# UPDIMOD-v1_0.net
KiCad netlist of a schematic drawn in EAGLE
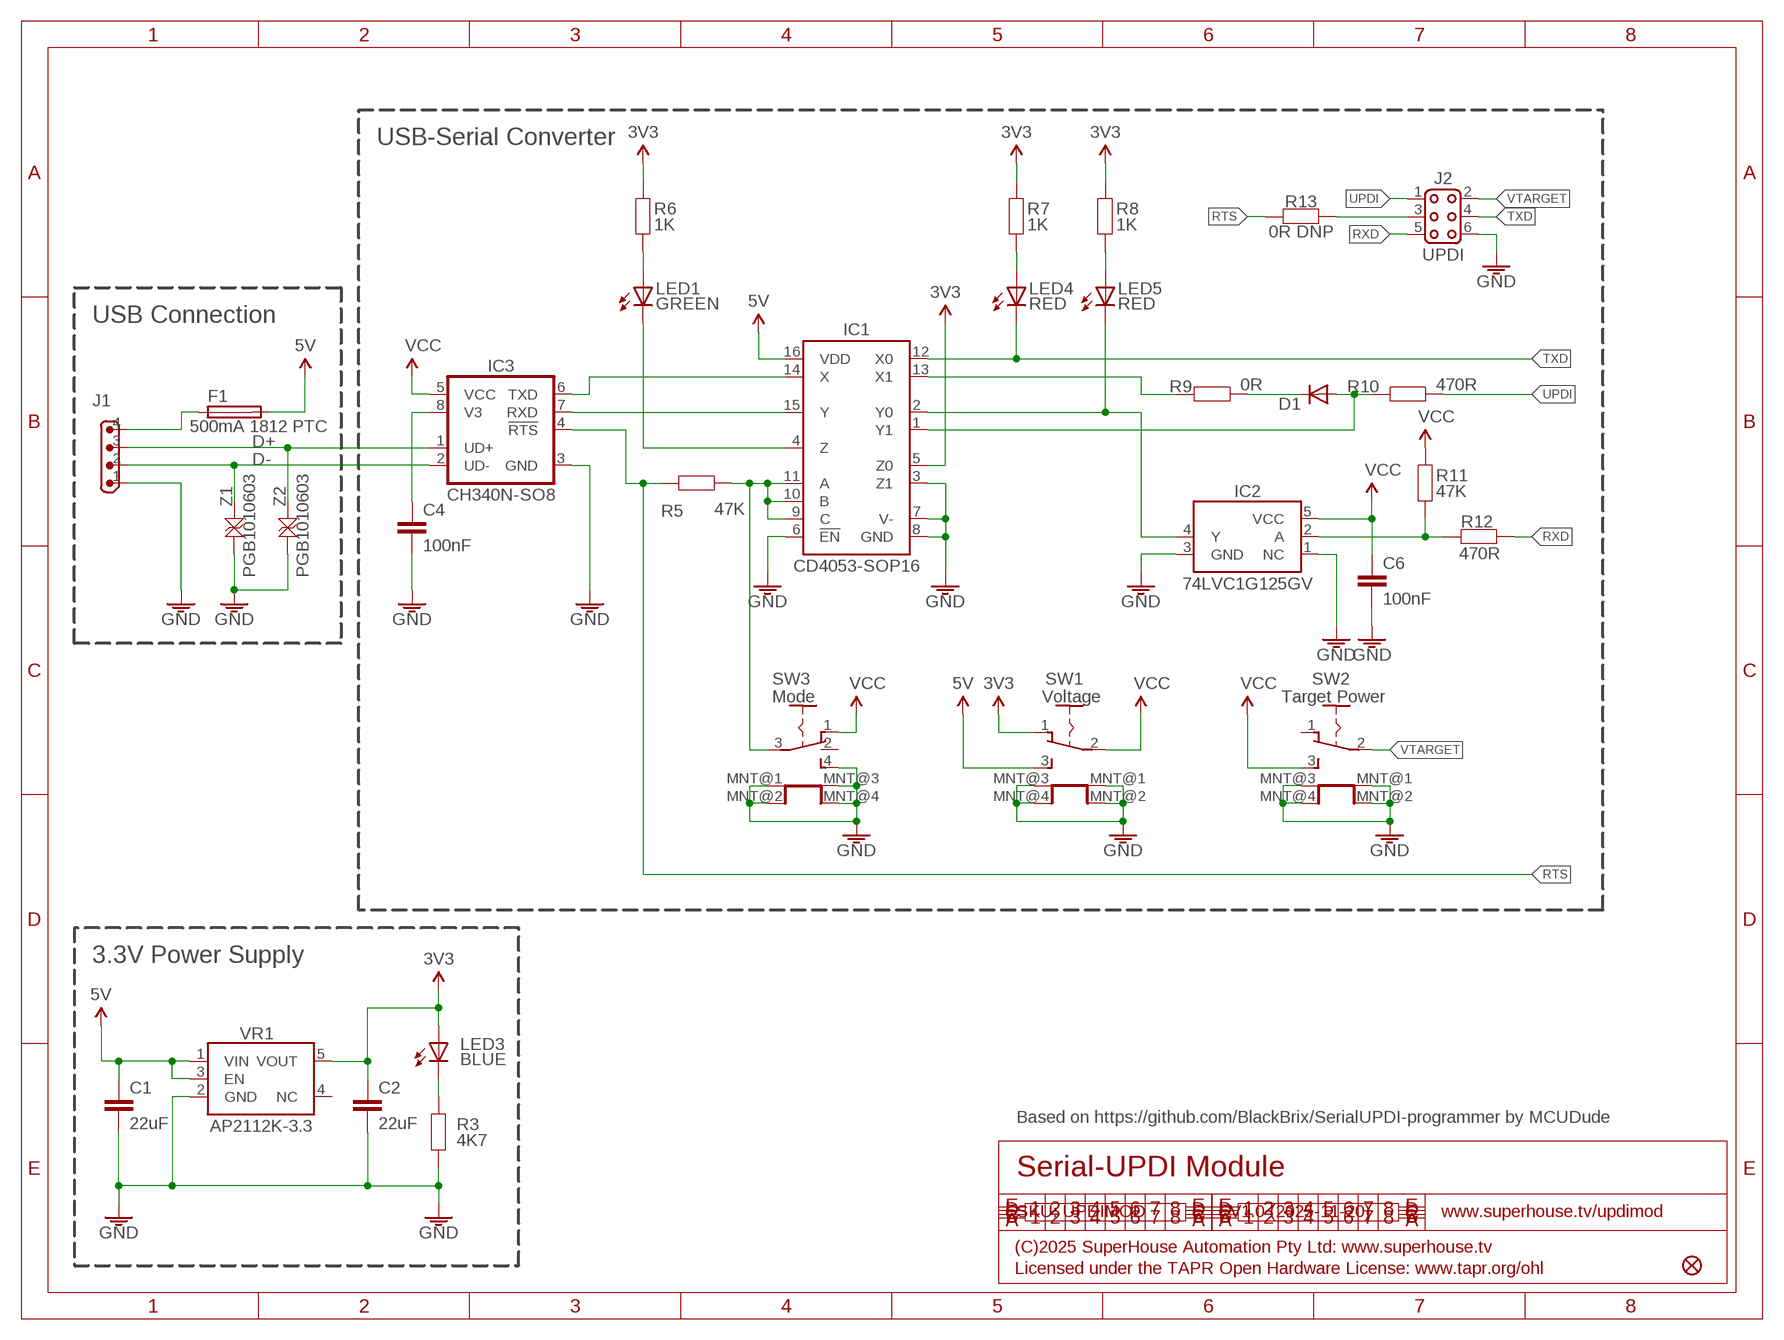
[diagram p0: schematic, sheet 1]

(export (version "E")
  (design (tool "Eeschema 10.0.6"))
  (components
    (comp (ref "C1")
      (value "22uF")
      (footprint "eagle-import:C0805")
      (libsource (lib "eagle-import") (part "CAP0805"))
    )
    (comp (ref "C2")
      (value "22uF")
      (footprint "eagle-import:C0805")
      (libsource (lib "eagle-import") (part "CAP0805"))
    )
    (comp (ref "C4")
      (value "100nF")
      (footprint "eagle-import:C0603")
      (libsource (lib "eagle-import") (part "SuperHouse-DiscreteSemi_11768461_CAP0603"))
    )
    (comp (ref "C6")
      (value "100nF")
      (footprint "eagle-import:C0603")
      (libsource (lib "eagle-import") (part "SuperHouse-DiscreteSemi_11768461_CAP0603"))
    )
    (comp (ref "D1")
      (value "DIODE-SOD123")
      (footprint "eagle-import:SOD-123")
      (libsource (lib "eagle-import") (part "DIODE-SOD123"))
    )
    (comp (ref "F1")
      (value "500mA 1812 PTC")
      (footprint "eagle-import:1206")
      (libsource (lib "eagle-import") (part "PTC-1206"))
    )
    (comp (ref "FID2")
      (value "FIDUCIAL1X2.5")
      (footprint "eagle-import:FIDUCIAL-1X2.5")
      (libsource (lib "eagle-import") (part "FIDUCIAL1X2.5"))
    )
    (comp (ref "IC1")
      (value "CD4053-SOP16")
      (footprint "eagle-import:SO16")
      (libsource (lib "eagle-import") (part "CD4053-SOP16"))
    )
    (comp (ref "IC2")
      (value "74LVC1G125GV")
      (footprint "eagle-import:SOT23-5")
      (libsource (lib "eagle-import") (part "74AHC1G14GW-SOT235"))
    )
    (comp (ref "IC3")
      (value "CH340N-SO8")
      (footprint "eagle-import:SOIC8")
      (libsource (lib "eagle-import") (part "CH340N-SO8"))
    )
    (comp (ref "J1")
      (value "M04-PIN-BELOW")
      (footprint "eagle-import:1X04-P-BELOW")
      (libsource (lib "eagle-import") (part "M04-PIN-BELOW"))
    )
    (comp (ref "J2")
      (value "UPDI")
      (footprint "eagle-import:2X03-S-BELOW")
      (libsource (lib "eagle-import") (part "M02X3-SOCKET-BELOW"))
    )
    (comp (ref "LED1")
      (value "GREEN")
      (footprint "eagle-import:LED-0603")
      (libsource (lib "eagle-import") (part "LED0603"))
    )
    (comp (ref "LED3")
      (value "BLUE")
      (footprint "eagle-import:LED-0603")
      (libsource (lib "eagle-import") (part "LED0603"))
    )
    (comp (ref "LED4")
      (value "RED")
      (footprint "eagle-import:LED-0603")
      (libsource (lib "eagle-import") (part "LED0603"))
    )
    (comp (ref "LED5")
      (value "RED")
      (footprint "eagle-import:LED-0603")
      (libsource (lib "eagle-import") (part "LED0603"))
    )
    (comp (ref "R3")
      (value "4K7")
      (footprint "eagle-import:R0603")
      (libsource (lib "eagle-import") (part "RESISTOR0603"))
    )
    (comp (ref "R5")
      (value "47K")
      (footprint "eagle-import:R0603")
      (libsource (lib "eagle-import") (part "RESISTOR0603"))
    )
    (comp (ref "R6")
      (value "1K")
      (footprint "eagle-import:R0603")
      (libsource (lib "eagle-import") (part "RESISTOR0603"))
    )
    (comp (ref "R7")
      (value "1K")
      (footprint "eagle-import:R0603")
      (libsource (lib "eagle-import") (part "RESISTOR0603"))
    )
    (comp (ref "R8")
      (value "1K")
      (footprint "eagle-import:R0603")
      (libsource (lib "eagle-import") (part "RESISTOR0603"))
    )
    (comp (ref "R9")
      (value "0R")
      (footprint "eagle-import:R0603")
      (libsource (lib "eagle-import") (part "RESISTOR0603"))
    )
    (comp (ref "R10")
      (value "470R")
      (footprint "eagle-import:R0603")
      (libsource (lib "eagle-import") (part "RESISTOR0603"))
    )
    (comp (ref "R11")
      (value "47K")
      (footprint "eagle-import:R0603")
      (libsource (lib "eagle-import") (part "RESISTOR0603"))
    )
    (comp (ref "R12")
      (value "470R")
      (footprint "eagle-import:R0603")
      (libsource (lib "eagle-import") (part "RESISTOR0603"))
    )
    (comp (ref "R13")
      (value "0R DNP")
      (footprint "eagle-import:R0603")
      (libsource (lib "eagle-import") (part "RESISTOR0603"))
    )
    (comp (ref "SW1")
      (value "Voltage")
      (footprint "eagle-import:MK-12C02")
      (libsource (lib "eagle-import") (part "SWITCH-SPDT-4TABSSMT"))
    )
    (comp (ref "SW2")
      (value "Target Power")
      (footprint "eagle-import:MK-12C02")
      (libsource (lib "eagle-import") (part "SWITCH-SPDT-4TABSSMT"))
    )
    (comp (ref "SW3")
      (value "Mode")
      (footprint "eagle-import:MK-13C02")
      (libsource (lib "eagle-import") (part "SWITCH-SP3T-4TABS"))
    )
    (comp (ref "VR1")
      (value "AP2112K-3.3")
      (footprint "eagle-import:SOT23-5")
      (libsource (lib "eagle-import") (part "AP2112KSOT25"))
    )
    (comp (ref "Z1")
      (value "PGB1010603")
      (footprint "eagle-import:TVS0603")
      (libsource (lib "eagle-import") (part "TVS0603"))
    )
    (comp (ref "Z2")
      (value "PGB1010603")
      (footprint "eagle-import:TVS0603")
      (libsource (lib "eagle-import") (part "TVS0603"))
    )
  )
  (nets
    (net (code "1") (name "/D+") (class "Default")
      (node (ref "IC3") (pin "1") (pinfunction "UD+_1") (pintype "bidirectional"))
      (node (ref "J1") (pin "3") (pinfunction "3_3") (pintype "passive"))
      (node (ref "Z2") (pin "2") (pinfunction "2_2") (pintype "passive"))
    )
    (net (code "2") (name "/D-") (class "Default")
      (node (ref "IC3") (pin "2") (pinfunction "UD-_2") (pintype "bidirectional"))
      (node (ref "J1") (pin "2") (pinfunction "2_2") (pintype "passive"))
      (node (ref "Z1") (pin "2") (pinfunction "2_2") (pintype "passive"))
    )
    (net (code "3") (name "3.3V") (class "Default")
      (node (ref "C2") (pin "1") (pinfunction "1_1") (pintype "passive"))
      (node (ref "IC1") (pin "5") (pinfunction "Z0_5") (pintype "passive"))
      (node (ref "LED3") (pin "A") (pinfunction "A_A") (pintype "passive"))
      (node (ref "R6") (pin "2") (pinfunction "2_2") (pintype "passive"))
      (node (ref "R7") (pin "2") (pinfunction "2_2") (pintype "passive"))
      (node (ref "R8") (pin "2") (pinfunction "2_2") (pintype "passive"))
      (node (ref "SW1") (pin "1") (pinfunction "A_1") (pintype "passive"))
      (node (ref "VR1") (pin "5") (pinfunction "VOUT_5") (pintype "bidirectional"))
    )
    (net (code "4") (name "5V") (class "Default")
      (node (ref "C1") (pin "1") (pinfunction "1_1") (pintype "passive"))
      (node (ref "F1") (pin "2") (pinfunction "2_2") (pintype "passive"))
      (node (ref "IC1") (pin "16") (pinfunction "VDD_16") (pintype "passive"))
      (node (ref "SW1") (pin "3") (pinfunction "B_3") (pintype "passive"))
      (node (ref "VR1") (pin "1") (pinfunction "VIN_1") (pintype "bidirectional"))
      (node (ref "VR1") (pin "3") (pinfunction "EN_3") (pintype "bidirectional"))
    )
    (net (code "5") (name "GND") (class "Default")
      (node (ref "C1") (pin "2") (pinfunction "2_2") (pintype "passive"))
      (node (ref "C2") (pin "2") (pinfunction "2_2") (pintype "passive"))
      (node (ref "C4") (pin "2") (pinfunction "2_2") (pintype "passive"))
      (node (ref "C6") (pin "2") (pinfunction "2_2") (pintype "passive"))
      (node (ref "IC1") (pin "3") (pinfunction "Z1_3") (pintype "passive"))
      (node (ref "IC1") (pin "6") (pinfunction "~{EN}_6") (pintype "passive"))
      (node (ref "IC1") (pin "7") (pinfunction "V-_7") (pintype "passive"))
      (node (ref "IC1") (pin "8") (pinfunction "GND_8") (pintype "passive"))
      (node (ref "IC2") (pin "1") (pinfunction "NC_1") (pintype "bidirectional"))
      (node (ref "IC2") (pin "3") (pinfunction "GND_3") (pintype "bidirectional"))
      (node (ref "IC3") (pin "3") (pinfunction "GND_3") (pintype "bidirectional"))
      (node (ref "J1") (pin "1") (pinfunction "1_1") (pintype "passive"))
      (node (ref "J2") (pin "6") (pinfunction "6_6") (pintype "passive"))
      (node (ref "R3") (pin "1") (pinfunction "1_1") (pintype "passive"))
      (node (ref "SW1") (pin "MNT@1") (pinfunction "MNT_MNT@1") (pintype "bidirectional"))
      (node (ref "SW1") (pin "MNT@2") (pinfunction "MNT_MNT@2") (pintype "bidirectional"))
      (node (ref "SW1") (pin "MNT@3") (pinfunction "MNT_MNT@3") (pintype "bidirectional"))
      (node (ref "SW1") (pin "MNT@4") (pinfunction "MNT_MNT@4") (pintype "bidirectional"))
      (node (ref "SW2") (pin "MNT@1") (pinfunction "MNT_MNT@1") (pintype "bidirectional"))
      (node (ref "SW2") (pin "MNT@2") (pinfunction "MNT_MNT@2") (pintype "bidirectional"))
      (node (ref "SW2") (pin "MNT@3") (pinfunction "MNT_MNT@3") (pintype "bidirectional"))
      (node (ref "SW2") (pin "MNT@4") (pinfunction "MNT_MNT@4") (pintype "bidirectional"))
      (node (ref "SW3") (pin "4") (pinfunction "C_4") (pintype "passive"))
      (node (ref "SW3") (pin "MNT@1") (pinfunction "MNT_MNT@1") (pintype "bidirectional"))
      (node (ref "SW3") (pin "MNT@2") (pinfunction "MNT_MNT@2") (pintype "bidirectional"))
      (node (ref "SW3") (pin "MNT@3") (pinfunction "MNT_MNT@3") (pintype "bidirectional"))
      (node (ref "SW3") (pin "MNT@4") (pinfunction "MNT_MNT@4") (pintype "bidirectional"))
      (node (ref "VR1") (pin "2") (pinfunction "GND_2") (pintype "bidirectional"))
      (node (ref "Z1") (pin "1") (pinfunction "1_1") (pintype "passive"))
      (node (ref "Z2") (pin "1") (pinfunction "1_1") (pintype "passive"))
    )
    (net (code "6") (name "Net-(D1-A)") (class "Default")
      (node (ref "D1") (pin "2") (pinfunction "A_2") (pintype "passive"))
      (node (ref "IC1") (pin "1") (pinfunction "Y1_1") (pintype "passive"))
      (node (ref "R10") (pin "2") (pinfunction "2_2") (pintype "passive"))
    )
    (net (code "7") (name "Net-(D1-C)") (class "Default")
      (node (ref "D1") (pin "1") (pinfunction "C_1") (pintype "passive"))
      (node (ref "R9") (pin "1") (pinfunction "1_1") (pintype "passive"))
    )
    (net (code "8") (name "Net-(F1-Pad1)") (class "Default")
      (node (ref "F1") (pin "1") (pinfunction "1_1") (pintype "passive"))
      (node (ref "J1") (pin "4") (pinfunction "4_4") (pintype "passive"))
    )
    (net (code "9") (name "Net-(IC1-A)") (class "Default")
      (node (ref "IC1") (pin "10") (pinfunction "B_10") (pintype "passive"))
      (node (ref "IC1") (pin "11") (pinfunction "A_11") (pintype "passive"))
      (node (ref "IC1") (pin "9") (pinfunction "C_9") (pintype "passive"))
      (node (ref "R5") (pin "1") (pinfunction "1_1") (pintype "passive"))
      (node (ref "SW3") (pin "3") (pinfunction "COM_3") (pintype "passive"))
    )
    (net (code "10") (name "Net-(IC1-X)") (class "Default")
      (node (ref "IC1") (pin "14") (pinfunction "X_14") (pintype "passive"))
      (node (ref "IC3") (pin "6") (pinfunction "TXD_6") (pintype "bidirectional"))
    )
    (net (code "11") (name "Net-(IC1-X1)") (class "Default")
      (node (ref "IC1") (pin "13") (pinfunction "X1_13") (pintype "passive"))
      (node (ref "R9") (pin "2") (pinfunction "2_2") (pintype "passive"))
    )
    (net (code "12") (name "Net-(IC1-Y)") (class "Default")
      (node (ref "IC1") (pin "15") (pinfunction "Y_15") (pintype "passive"))
      (node (ref "IC3") (pin "7") (pinfunction "RXD_7") (pintype "bidirectional"))
    )
    (net (code "13") (name "Net-(IC1-Y0)") (class "Default")
      (node (ref "IC1") (pin "2") (pinfunction "Y0_2") (pintype "passive"))
      (node (ref "IC2") (pin "4") (pinfunction "Y_4") (pintype "bidirectional"))
      (node (ref "LED5") (pin "C") (pinfunction "C_C") (pintype "passive"))
    )
    (net (code "14") (name "Net-(IC1-Z)") (class "Default")
      (node (ref "IC1") (pin "4") (pinfunction "Z_4") (pintype "passive"))
      (node (ref "LED1") (pin "C") (pinfunction "C_C") (pintype "passive"))
    )
    (net (code "15") (name "Net-(IC2-A)") (class "Default")
      (node (ref "IC2") (pin "2") (pinfunction "A_2") (pintype "bidirectional"))
      (node (ref "R11") (pin "1") (pinfunction "1_1") (pintype "passive"))
      (node (ref "R12") (pin "2") (pinfunction "2_2") (pintype "passive"))
    )
    (net (code "16") (name "Net-(IC3-V3)") (class "Default")
      (node (ref "C4") (pin "1") (pinfunction "1_1") (pintype "passive"))
      (node (ref "IC3") (pin "8") (pinfunction "V3_8") (pintype "bidirectional"))
    )
    (net (code "17") (name "Net-(J2-Pad3)") (class "Default")
      (node (ref "J2") (pin "3") (pinfunction "3_3") (pintype "passive"))
      (node (ref "R13") (pin "1") (pinfunction "1_1") (pintype "passive"))
    )
    (net (code "18") (name "Net-(LED1-PadA)") (class "Default")
      (node (ref "LED1") (pin "A") (pinfunction "A_A") (pintype "passive"))
      (node (ref "R6") (pin "1") (pinfunction "1_1") (pintype "passive"))
    )
    (net (code "19") (name "Net-(LED3-PadC)") (class "Default")
      (node (ref "LED3") (pin "C") (pinfunction "C_C") (pintype "passive"))
      (node (ref "R3") (pin "2") (pinfunction "2_2") (pintype "passive"))
    )
    (net (code "20") (name "Net-(LED4-PadA)") (class "Default")
      (node (ref "LED4") (pin "A") (pinfunction "A_A") (pintype "passive"))
      (node (ref "R7") (pin "1") (pinfunction "1_1") (pintype "passive"))
    )
    (net (code "21") (name "Net-(LED5-PadA)") (class "Default")
      (node (ref "LED5") (pin "A") (pinfunction "A_A") (pintype "passive"))
      (node (ref "R8") (pin "1") (pinfunction "1_1") (pintype "passive"))
    )
    (net (code "22") (name "RTS") (class "Default")
      (node (ref "IC3") (pin "4") (pinfunction "~{RTS}_4") (pintype "bidirectional"))
      (node (ref "R13") (pin "2") (pinfunction "2_2") (pintype "passive"))
      (node (ref "R5") (pin "2") (pinfunction "2_2") (pintype "passive"))
    )
    (net (code "23") (name "RXD") (class "Default")
      (node (ref "J2") (pin "5") (pinfunction "5_5") (pintype "passive"))
      (node (ref "R12") (pin "1") (pinfunction "1_1") (pintype "passive"))
    )
    (net (code "24") (name "TXD") (class "Default")
      (node (ref "IC1") (pin "12") (pinfunction "X0_12") (pintype "passive"))
      (node (ref "J2") (pin "4") (pinfunction "4_4") (pintype "passive"))
      (node (ref "LED4") (pin "C") (pinfunction "C_C") (pintype "passive"))
    )
    (net (code "25") (name "UPDI") (class "Default")
      (node (ref "J2") (pin "1") (pinfunction "1_1") (pintype "passive"))
      (node (ref "R10") (pin "1") (pinfunction "1_1") (pintype "passive"))
    )
    (net (code "26") (name "VCC") (class "Default")
      (node (ref "C6") (pin "1") (pinfunction "1_1") (pintype "passive"))
      (node (ref "IC2") (pin "5") (pinfunction "VCC_5") (pintype "bidirectional"))
      (node (ref "IC3") (pin "5") (pinfunction "VCC_5") (pintype "bidirectional"))
      (node (ref "R11") (pin "2") (pinfunction "2_2") (pintype "passive"))
      (node (ref "SW1") (pin "2") (pinfunction "COM_2") (pintype "passive"))
      (node (ref "SW2") (pin "3") (pinfunction "B_3") (pintype "passive"))
      (node (ref "SW3") (pin "1") (pinfunction "A_1") (pintype "passive"))
    )
    (net (code "27") (name "VTARGET") (class "Default")
      (node (ref "J2") (pin "2") (pinfunction "2_2") (pintype "passive"))
      (node (ref "SW2") (pin "2") (pinfunction "COM_2") (pintype "passive"))
    )
    (net (code "28") (name "unconnected-(SW2-A-Pad1)") (class "Default")
      (node (ref "SW2") (pin "1") (pinfunction "A_1") (pintype "passive"))
    )
    (net (code "29") (name "unconnected-(SW3-B-Pad2)") (class "Default")
      (node (ref "SW3") (pin "2") (pinfunction "B_2") (pintype "passive"))
    )
    (net (code "30") (name "unconnected-(VR1-NC-Pad4)") (class "Default")
      (node (ref "VR1") (pin "4") (pinfunction "NC_4") (pintype "bidirectional"))
    )
  )
)
